# slew_rate_control.net
KiCad netlist of a schematic drawn in EAGLE
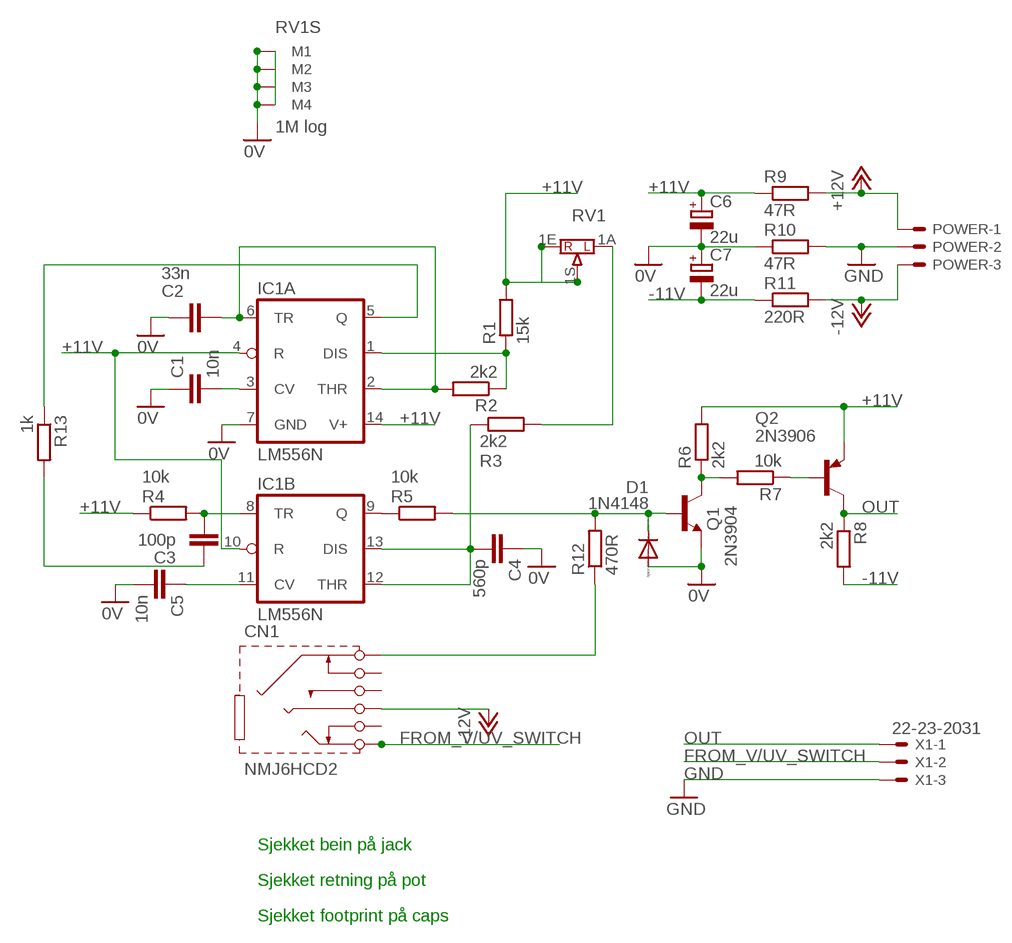
[diagram p0: schematic, sheet 1]

(export (version "E")
  (design (tool "Eeschema 10.0.6"))
  (components
    (comp (ref "C1")
      (value "10n")
      (footprint "eagle-import:C025-025X050")
      (libsource (lib "eagle-import") (part "C-EU025-025X050"))
    )
    (comp (ref "C2")
      (value "33n")
      (footprint "eagle-import:C075-032X103")
      (libsource (lib "eagle-import") (part "C-EU075-032X103"))
    )
    (comp (ref "C3")
      (value "100p")
      (footprint "eagle-import:C025-025X050")
      (libsource (lib "eagle-import") (part "C-EU025-025X050"))
    )
    (comp (ref "C4")
      (value "560p")
      (footprint "eagle-import:C025_050-025X075")
      (libsource (lib "eagle-import") (part "C-EU025_050-025X075"))
    )
    (comp (ref "C5")
      (value "10n")
      (footprint "eagle-import:C025-025X050")
      (libsource (lib "eagle-import") (part "C-EU025-025X050"))
    )
    (comp (ref "C6")
      (value "22u")
      (footprint "eagle-import:E2,5-5")
      (libsource (lib "eagle-import") (part "CPOL-EUE2.5-5"))
    )
    (comp (ref "C7")
      (value "22u")
      (footprint "eagle-import:E2,5-5")
      (libsource (lib "eagle-import") (part "CPOL-EUE2.5-5"))
    )
    (comp (ref "CN1")
      (value "NMJ6HCD2")
      (footprint "eagle-import:NMJ6HCD2")
      (libsource (lib "eagle-import") (part "NMJ6HCD2"))
    )
    (comp (ref "D1")
      (value "1N4148")
      (footprint "eagle-import:DO35-5J")
      (libsource (lib "eagle-import") (part "1N4148DOJ35-5"))
    )
    (comp (ref "IC1")
      (value "LM556N")
      (footprint "eagle-import:DIL14")
      (libsource (lib "eagle-import") (part "556NLM"))
    )
    (comp (ref "POWER")
      (value "KK-156-3")
      (footprint "eagle-import:KK-156-3")
      (libsource (lib "eagle-import") (part "KK-156-3"))
    )
    (comp (ref "Q1")
      (value "2N3904")
      (footprint "eagle-import:TO92")
      (libsource (lib "eagle-import") (part "2N3904"))
    )
    (comp (ref "Q2")
      (value "2N3906")
      (footprint "eagle-import:TO92")
      (libsource (lib "eagle-import") (part "2N3906"))
    )
    (comp (ref "R1")
      (value "15k")
      (footprint "eagle-import:0207_7")
      (libsource (lib "eagle-import") (part "R-EU_0207/7"))
    )
    (comp (ref "R2")
      (value "2k2")
      (footprint "eagle-import:0207_7")
      (libsource (lib "eagle-import") (part "R-EU_0207/7"))
    )
    (comp (ref "R3")
      (value "2k2")
      (footprint "eagle-import:0207_7")
      (libsource (lib "eagle-import") (part "R-EU_0207/7"))
    )
    (comp (ref "R4")
      (value "10k")
      (footprint "eagle-import:0207_7")
      (libsource (lib "eagle-import") (part "R-EU_0207/7"))
    )
    (comp (ref "R5")
      (value "10k")
      (footprint "eagle-import:0207_7")
      (libsource (lib "eagle-import") (part "R-EU_0207/7"))
    )
    (comp (ref "R6")
      (value "2k2")
      (footprint "eagle-import:0207_7")
      (libsource (lib "eagle-import") (part "R-EU_0207/7"))
    )
    (comp (ref "R7")
      (value "10k")
      (footprint "eagle-import:0207_7")
      (libsource (lib "eagle-import") (part "R-EU_0207/7"))
    )
    (comp (ref "R8")
      (value "2k2")
      (footprint "eagle-import:0207_7")
      (libsource (lib "eagle-import") (part "R-EU_0207/7"))
    )
    (comp (ref "R9")
      (value "47R")
      (footprint "eagle-import:0207_7")
      (libsource (lib "eagle-import") (part "R-EU_0207/7"))
    )
    (comp (ref "R10")
      (value "47R")
      (footprint "eagle-import:0207_7")
      (libsource (lib "eagle-import") (part "R-EU_0207/7"))
    )
    (comp (ref "R11")
      (value "220R")
      (footprint "eagle-import:0207_7")
      (libsource (lib "eagle-import") (part "R-EU_0207/7"))
    )
    (comp (ref "R12")
      (value "470R")
      (footprint "eagle-import:0207_7")
      (libsource (lib "eagle-import") (part "R-EU_0207/7"))
    )
    (comp (ref "R13")
      (value "1k")
      (footprint "eagle-import:0207_7")
      (libsource (lib "eagle-import") (part "R-EU_0207/7"))
    )
    (comp (ref "RV1")
      (value "1M log")
      (footprint "eagle-import:POT16_W_BRACKET")
      (libsource (lib "eagle-import") (part "POT16_W_BRACKET{dblquote}{dblquote}"))
    )
    (comp (ref "X1")
      (value "22-23-2031")
      (footprint "eagle-import:22-23-2031")
      (fields (field (name "MF") "MOLEX"))
      (libsource (lib "eagle-import") (part "22-23-2031"))
    )
  )
  (nets
    (net (code "1") (name "+12V") (class "Default")
      (node (ref "POWER") (pin "1") (pinfunction "S_1") (pintype "passive"))
      (node (ref "R9") (pin "2") (pinfunction "2_2") (pintype "passive"))
    )
    (net (code "2") (name "-12V") (class "Default")
      (node (ref "CN1") (pin "R") (pinfunction "RING_R") (pintype "passive"))
      (node (ref "POWER") (pin "3") (pinfunction "S_3") (pintype "passive"))
      (node (ref "R11") (pin "2") (pinfunction "2_2") (pintype "passive"))
    )
    (net (code "3") (name "/+11V") (class "Default")
      (node (ref "C6") (pin "+") (pinfunction "+_+") (pintype "passive"))
      (node (ref "IC1") (pin "10") (pinfunction "R_10") (pintype "input"))
      (node (ref "IC1") (pin "14") (pinfunction "V+_14") (pintype "power_in"))
      (node (ref "IC1") (pin "4") (pinfunction "R_4") (pintype "input"))
      (node (ref "Q2") (pin "3") (pinfunction "E_3") (pintype "passive"))
      (node (ref "R1") (pin "2") (pinfunction "2_2") (pintype "passive"))
      (node (ref "R4") (pin "1") (pinfunction "1_1") (pintype "passive"))
      (node (ref "R6") (pin "2") (pinfunction "2_2") (pintype "passive"))
      (node (ref "R9") (pin "1") (pinfunction "1_1") (pintype "passive"))
      (node (ref "RV1") (pin "1E") (pinfunction "1E_1E") (pintype "passive"))
      (node (ref "RV1") (pin "1S") (pinfunction "1S_1S") (pintype "passive"))
    )
    (net (code "4") (name "/-11V") (class "Default")
      (node (ref "C7") (pin "-") (pinfunction "-_-") (pintype "passive"))
      (node (ref "R11") (pin "1") (pinfunction "1_1") (pintype "passive"))
      (node (ref "R8") (pin "2") (pinfunction "2_2") (pintype "passive"))
    )
    (net (code "5") (name "/FROM_V{slash}UV_SWITCH") (class "Default")
      (node (ref "CN1") (pin "T") (pinfunction "TIP_T") (pintype "passive"))
      (node (ref "X1") (pin "2") (pinfunction "S_2") (pintype "passive"))
    )
    (net (code "6") (name "/OUT") (class "Default")
      (node (ref "Q2") (pin "1") (pinfunction "C_1") (pintype "passive"))
      (node (ref "R8") (pin "1") (pinfunction "1_1") (pintype "passive"))
      (node (ref "X1") (pin "1") (pinfunction "S_1") (pintype "passive"))
    )
    (net (code "7") (name "0V") (class "Default")
      (node (ref "C1") (pin "1") (pinfunction "1_1") (pintype "passive"))
      (node (ref "C2") (pin "2") (pinfunction "2_2") (pintype "passive"))
      (node (ref "C4") (pin "1") (pinfunction "1_1") (pintype "passive"))
      (node (ref "C5") (pin "2") (pinfunction "2_2") (pintype "passive"))
      (node (ref "C6") (pin "-") (pinfunction "-_-") (pintype "passive"))
      (node (ref "C7") (pin "+") (pinfunction "+_+") (pintype "passive"))
      (node (ref "D1") (pin "A") (pinfunction "A_A") (pintype "passive"))
      (node (ref "IC1") (pin "7") (pinfunction "GND_7") (pintype "power_in"))
      (node (ref "Q1") (pin "3") (pinfunction "E_3") (pintype "passive"))
      (node (ref "R10") (pin "1") (pinfunction "1_1") (pintype "passive"))
      (node (ref "RV1") (pin "M1") (pinfunction "M1_M1") (pintype "passive"))
      (node (ref "RV1") (pin "M2") (pinfunction "M2_M2") (pintype "passive"))
      (node (ref "RV1") (pin "M3") (pinfunction "M3_M3") (pintype "passive"))
      (node (ref "RV1") (pin "M4") (pinfunction "M4_M4") (pintype "passive"))
    )
    (net (code "8") (name "GND") (class "Default")
      (node (ref "POWER") (pin "2") (pinfunction "S_2") (pintype "passive"))
      (node (ref "R10") (pin "2") (pinfunction "2_2") (pintype "passive"))
      (node (ref "X1") (pin "3") (pinfunction "S_3") (pintype "passive"))
    )
    (net (code "9") (name "Net-(C3-Pad1)") (class "Default")
      (node (ref "C3") (pin "1") (pinfunction "1_1") (pintype "passive"))
      (node (ref "R13") (pin "2") (pinfunction "2_2") (pintype "passive"))
    )
    (net (code "10") (name "Net-(CN1-SLEEVE)") (class "Default")
      (node (ref "CN1") (pin "S") (pinfunction "SLEEVE_S") (pintype "passive"))
      (node (ref "R12") (pin "1") (pinfunction "1_1") (pintype "passive"))
    )
    (net (code "11") (name "Net-(IC1A-CV)") (class "Default")
      (node (ref "C1") (pin "2") (pinfunction "2_2") (pintype "passive"))
      (node (ref "IC1") (pin "3") (pinfunction "CV_3") (pintype "input"))
    )
    (net (code "12") (name "Net-(IC1A-DIS)") (class "Default")
      (node (ref "IC1") (pin "1") (pinfunction "DIS_1") (pintype "input"))
      (node (ref "R1") (pin "1") (pinfunction "1_1") (pintype "passive"))
      (node (ref "R2") (pin "1") (pinfunction "1_1") (pintype "passive"))
    )
    (net (code "13") (name "Net-(IC1A-Q)") (class "Default")
      (node (ref "IC1") (pin "5") (pinfunction "Q_5") (pintype "output"))
      (node (ref "R13") (pin "1") (pinfunction "1_1") (pintype "passive"))
    )
    (net (code "14") (name "Net-(IC1A-THR)") (class "Default")
      (node (ref "C2") (pin "1") (pinfunction "1_1") (pintype "passive"))
      (node (ref "IC1") (pin "2") (pinfunction "THR_2") (pintype "input"))
      (node (ref "IC1") (pin "6") (pinfunction "TR_6") (pintype "input"))
      (node (ref "R2") (pin "2") (pinfunction "2_2") (pintype "passive"))
    )
    (net (code "15") (name "Net-(IC1B-CV)") (class "Default")
      (node (ref "C5") (pin "1") (pinfunction "1_1") (pintype "passive"))
      (node (ref "IC1") (pin "11") (pinfunction "CV_11") (pintype "input"))
    )
    (net (code "16") (name "Net-(IC1B-DIS)") (class "Default")
      (node (ref "C4") (pin "2") (pinfunction "2_2") (pintype "passive"))
      (node (ref "IC1") (pin "12") (pinfunction "THR_12") (pintype "input"))
      (node (ref "IC1") (pin "13") (pinfunction "DIS_13") (pintype "input"))
      (node (ref "R3") (pin "1") (pinfunction "1_1") (pintype "passive"))
    )
    (net (code "17") (name "Net-(IC1B-Q)") (class "Default")
      (node (ref "IC1") (pin "9") (pinfunction "Q_9") (pintype "output"))
      (node (ref "R5") (pin "1") (pinfunction "1_1") (pintype "passive"))
    )
    (net (code "18") (name "Net-(IC1B-TR)") (class "Default")
      (node (ref "C3") (pin "2") (pinfunction "2_2") (pintype "passive"))
      (node (ref "IC1") (pin "8") (pinfunction "TR_8") (pintype "input"))
      (node (ref "R4") (pin "2") (pinfunction "2_2") (pintype "passive"))
    )
    (net (code "19") (name "Net-(Q1-B)") (class "Default")
      (node (ref "D1") (pin "C") (pinfunction "C_C") (pintype "passive"))
      (node (ref "Q1") (pin "2") (pinfunction "B_2") (pintype "passive"))
      (node (ref "R12") (pin "2") (pinfunction "2_2") (pintype "passive"))
      (node (ref "R5") (pin "2") (pinfunction "2_2") (pintype "passive"))
    )
    (net (code "20") (name "Net-(Q1-C)") (class "Default")
      (node (ref "Q1") (pin "1") (pinfunction "C_1") (pintype "passive"))
      (node (ref "R6") (pin "1") (pinfunction "1_1") (pintype "passive"))
      (node (ref "R7") (pin "2") (pinfunction "2_2") (pintype "passive"))
    )
    (net (code "21") (name "Net-(Q2-B)") (class "Default")
      (node (ref "Q2") (pin "2") (pinfunction "B_2") (pintype "passive"))
      (node (ref "R7") (pin "1") (pinfunction "1_1") (pintype "passive"))
    )
    (net (code "22") (name "Net-(R3-Pad2)") (class "Default")
      (node (ref "R3") (pin "2") (pinfunction "2_2") (pintype "passive"))
      (node (ref "RV1") (pin "1A") (pinfunction "1A_1A") (pintype "passive"))
    )
    (net (code "23") (name "unconnected-(CN1-RING-S-PadRN)") (class "Default")
      (node (ref "CN1") (pin "RN") (pinfunction "RING-S_RN") (pintype "passive"))
    )
    (net (code "24") (name "unconnected-(CN1-SLEEVE-S-PadSN)") (class "Default")
      (node (ref "CN1") (pin "SN") (pinfunction "SLEEVE-S_SN") (pintype "passive"))
    )
    (net (code "25") (name "unconnected-(CN1-TIP-S-PadTN)") (class "Default")
      (node (ref "CN1") (pin "TN") (pinfunction "TIP-S_TN") (pintype "passive"))
    )
  )
)
